# ntp_clock.net
KiCad netlist of a schematic drawn in EAGLE
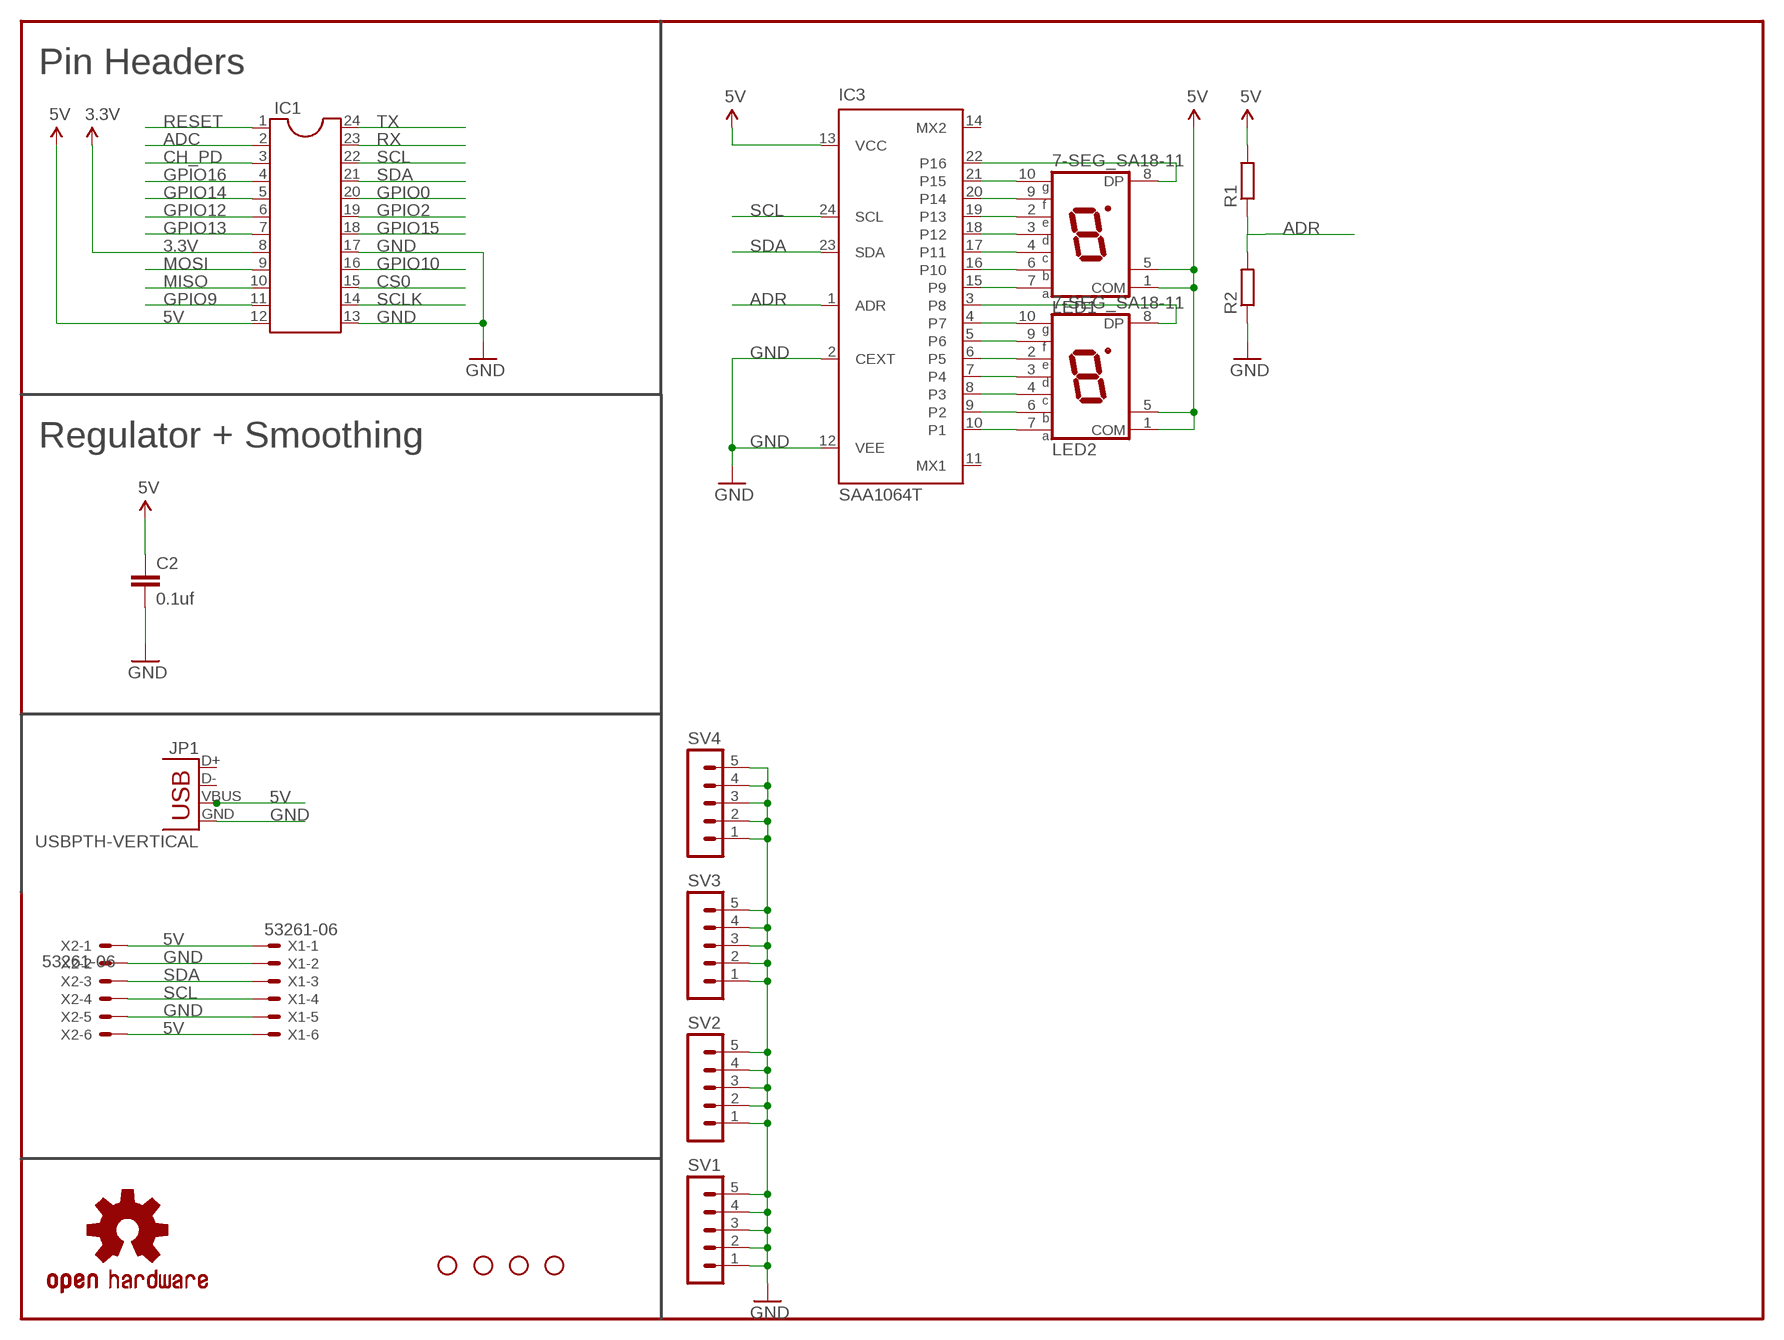
[diagram p0: schematic, sheet 1]

(export (version "E")
  (design (tool "Eeschema 10.0.6"))
  (components
    (comp (ref "C2")
      (value "0.1uf")
      (footprint "eagle-import:1206")
      (libsource (lib "eagle-import") (part "CAP1206"))
    )
    (comp (ref "FRAME1")
      (value "FRAME-LETTERNO_PACKAGE")
      (footprint "eagle-import:DUMMY")
      (fields (field (name "DESIGNER") "Nobody"))
      (libsource (lib "eagle-import") (part "FRAME-LETTERNO_PACKAGE"))
    )
    (comp (ref "IC1")
      (value "DIL24-9")
      (footprint "eagle-import:DIL24-9")
      (libsource (lib "eagle-import") (part "DIL24-9"))
    )
    (comp (ref "IC3")
      (value "SAA1064T")
      (footprint "eagle-import:SO24")
      (fields (field (name "MPN") "SAA1064T/N2,118"))
      (libsource (lib "eagle-import") (part "SAA1064T"))
    )
    (comp (ref "JP1")
      (value "USBPTH-VERTICAL")
      (footprint "eagle-import:USB-B-PTH-VERTICAL")
      (libsource (lib "eagle-import") (part "USBPTH-VERTICAL"))
    )
    (comp (ref "LED1")
      (value "7-SEG_SA18-11")
      (footprint "eagle-import:SA18-11")
      (libsource (lib "eagle-import") (part "7-SEG_SA18-11"))
    )
    (comp (ref "LED2")
      (value "7-SEG_SA18-11")
      (footprint "eagle-import:SA18-11")
      (libsource (lib "eagle-import") (part "7-SEG_SA18-11"))
    )
    (comp (ref "LOGO1")
      (value "OSHW-LOGOS")
      (footprint "eagle-import:OSHW-LOGO-S")
      (libsource (lib "eagle-import") (part "OSHW-LOGOS"))
    )
    (comp (ref "R1")
      (value "R-EU_0207/12")
      (footprint "eagle-import:0207_12")
      (libsource (lib "eagle-import") (part "R-EU_0207/12"))
    )
    (comp (ref "R2")
      (value "R-EU_0207/12")
      (footprint "eagle-import:0207_12")
      (libsource (lib "eagle-import") (part "R-EU_0207/12"))
    )
    (comp (ref "STANDOFF1")
      (value "STAND-OFF")
      (footprint "eagle-import:STAND-OFF")
      (libsource (lib "eagle-import") (part "STAND-OFF"))
    )
    (comp (ref "STANDOFF2")
      (value "STAND-OFF")
      (footprint "eagle-import:STAND-OFF")
      (libsource (lib "eagle-import") (part "STAND-OFF"))
    )
    (comp (ref "STANDOFF3")
      (value "STAND-OFF")
      (footprint "eagle-import:STAND-OFF")
      (libsource (lib "eagle-import") (part "STAND-OFF"))
    )
    (comp (ref "STANDOFF4")
      (value "STAND-OFF")
      (footprint "eagle-import:STAND-OFF")
      (libsource (lib "eagle-import") (part "STAND-OFF"))
    )
    (comp (ref "SV1")
      (value "MA05-1")
      (footprint "eagle-import:MA05-1")
      (libsource (lib "eagle-import") (part "MA05-1"))
    )
    (comp (ref "SV2")
      (value "MA05-1")
      (footprint "eagle-import:MA05-1")
      (libsource (lib "eagle-import") (part "MA05-1"))
    )
    (comp (ref "SV3")
      (value "MA05-1")
      (footprint "eagle-import:MA05-1")
      (libsource (lib "eagle-import") (part "MA05-1"))
    )
    (comp (ref "SV4")
      (value "MA05-1")
      (footprint "eagle-import:MA05-1")
      (libsource (lib "eagle-import") (part "MA05-1"))
    )
    (comp (ref "X1")
      (value "53261-06")
      (footprint "eagle-import:53261-06")
      (libsource (lib "eagle-import") (part "53?-06261"))
    )
    (comp (ref "X2")
      (value "53261-06")
      (footprint "eagle-import:53261-06")
      (libsource (lib "eagle-import") (part "53?-06261"))
    )
  )
  (nets
    (net (code "1") (name "/ADC") (class "Default")
      (node (ref "IC1") (pin "2") (pinfunction "2_2") (pintype "passive"))
    )
    (net (code "2") (name "/ADR") (class "Default")
      (node (ref "IC3") (pin "1") (pinfunction "ADR_1") (pintype "input"))
      (node (ref "R1") (pin "1") (pinfunction "1_1") (pintype "passive"))
      (node (ref "R2") (pin "2") (pinfunction "2_2") (pintype "passive"))
    )
    (net (code "3") (name "/CH_PD") (class "Default")
      (node (ref "IC1") (pin "3") (pinfunction "3_3") (pintype "passive"))
    )
    (net (code "4") (name "/CS0") (class "Default")
      (node (ref "IC1") (pin "15") (pinfunction "15_15") (pintype "passive"))
    )
    (net (code "5") (name "/GPIO0") (class "Default")
      (node (ref "IC1") (pin "20") (pinfunction "20_20") (pintype "passive"))
    )
    (net (code "6") (name "/GPIO2") (class "Default")
      (node (ref "IC1") (pin "19") (pinfunction "19_19") (pintype "passive"))
    )
    (net (code "7") (name "/GPIO9") (class "Default")
      (node (ref "IC1") (pin "11") (pinfunction "11_11") (pintype "passive"))
    )
    (net (code "8") (name "/GPIO10") (class "Default")
      (node (ref "IC1") (pin "16") (pinfunction "16_16") (pintype "passive"))
    )
    (net (code "9") (name "/GPIO12") (class "Default")
      (node (ref "IC1") (pin "6") (pinfunction "6_6") (pintype "passive"))
    )
    (net (code "10") (name "/GPIO13") (class "Default")
      (node (ref "IC1") (pin "7") (pinfunction "7_7") (pintype "passive"))
    )
    (net (code "11") (name "/GPIO14") (class "Default")
      (node (ref "IC1") (pin "5") (pinfunction "5_5") (pintype "passive"))
    )
    (net (code "12") (name "/GPIO15") (class "Default")
      (node (ref "IC1") (pin "18") (pinfunction "18_18") (pintype "passive"))
    )
    (net (code "13") (name "/GPIO16") (class "Default")
      (node (ref "IC1") (pin "4") (pinfunction "4_4") (pintype "passive"))
    )
    (net (code "14") (name "/MISO") (class "Default")
      (node (ref "IC1") (pin "10") (pinfunction "10_10") (pintype "passive"))
    )
    (net (code "15") (name "/MOSI") (class "Default")
      (node (ref "IC1") (pin "9") (pinfunction "9_9") (pintype "passive"))
    )
    (net (code "16") (name "/RESET") (class "Default")
      (node (ref "IC1") (pin "1") (pinfunction "1_1") (pintype "passive"))
    )
    (net (code "17") (name "/RX") (class "Default")
      (node (ref "IC1") (pin "23") (pinfunction "23_23") (pintype "passive"))
    )
    (net (code "18") (name "/SCL") (class "Default")
      (node (ref "IC1") (pin "22") (pinfunction "22_22") (pintype "passive"))
      (node (ref "IC3") (pin "24") (pinfunction "SCL_24") (pintype "input"))
      (node (ref "X1") (pin "4") (pinfunction "S_4") (pintype "passive"))
      (node (ref "X2") (pin "4") (pinfunction "S_4") (pintype "passive"))
    )
    (net (code "19") (name "/SCLK") (class "Default")
      (node (ref "IC1") (pin "14") (pinfunction "14_14") (pintype "passive"))
    )
    (net (code "20") (name "/SDA") (class "Default")
      (node (ref "IC1") (pin "21") (pinfunction "21_21") (pintype "passive"))
      (node (ref "IC3") (pin "23") (pinfunction "SDA_23") (pintype "input"))
      (node (ref "X1") (pin "3") (pinfunction "S_3") (pintype "passive"))
      (node (ref "X2") (pin "3") (pinfunction "S_3") (pintype "passive"))
    )
    (net (code "21") (name "/TX") (class "Default")
      (node (ref "IC1") (pin "24") (pinfunction "24_24") (pintype "passive"))
    )
    (net (code "22") (name "3.3V") (class "Default")
      (node (ref "IC1") (pin "8") (pinfunction "8_8") (pintype "passive"))
    )
    (net (code "23") (name "5V") (class "Default")
      (node (ref "C2") (pin "1") (pinfunction "1_1") (pintype "passive"))
      (node (ref "IC1") (pin "12") (pinfunction "12_12") (pintype "passive"))
      (node (ref "IC3") (pin "13") (pinfunction "VCC_13") (pintype "power_in"))
      (node (ref "JP1") (pin "VBUS") (pinfunction "VBUS_VBUS") (pintype "bidirectional"))
      (node (ref "LED1") (pin "1") (pinfunction "COM_1") (pintype "passive"))
      (node (ref "LED1") (pin "5") (pinfunction "COM_5") (pintype "passive"))
      (node (ref "LED2") (pin "1") (pinfunction "COM_1") (pintype "passive"))
      (node (ref "LED2") (pin "5") (pinfunction "COM_5") (pintype "passive"))
      (node (ref "R1") (pin "2") (pinfunction "2_2") (pintype "passive"))
      (node (ref "X1") (pin "1") (pinfunction "S_1") (pintype "passive"))
      (node (ref "X1") (pin "6") (pinfunction "S_6") (pintype "passive"))
      (node (ref "X2") (pin "1") (pinfunction "S_1") (pintype "passive"))
      (node (ref "X2") (pin "6") (pinfunction "S_6") (pintype "passive"))
    )
    (net (code "24") (name "GND") (class "Default")
      (node (ref "C2") (pin "2") (pinfunction "2_2") (pintype "passive"))
      (node (ref "IC1") (pin "13") (pinfunction "13_13") (pintype "passive"))
      (node (ref "IC1") (pin "17") (pinfunction "17_17") (pintype "passive"))
      (node (ref "IC3") (pin "12") (pinfunction "VEE_12") (pintype "power_in"))
      (node (ref "IC3") (pin "2") (pinfunction "CEXT_2") (pintype "input"))
      (node (ref "JP1") (pin "GND") (pinfunction "GND_GND") (pintype "bidirectional"))
      (node (ref "R2") (pin "1") (pinfunction "1_1") (pintype "passive"))
      (node (ref "SV1") (pin "1") (pinfunction "1_1") (pintype "passive"))
      (node (ref "SV1") (pin "2") (pinfunction "2_2") (pintype "passive"))
      (node (ref "SV1") (pin "3") (pinfunction "3_3") (pintype "passive"))
      (node (ref "SV1") (pin "4") (pinfunction "4_4") (pintype "passive"))
      (node (ref "SV1") (pin "5") (pinfunction "5_5") (pintype "passive"))
      (node (ref "SV2") (pin "1") (pinfunction "1_1") (pintype "passive"))
      (node (ref "SV2") (pin "2") (pinfunction "2_2") (pintype "passive"))
      (node (ref "SV2") (pin "3") (pinfunction "3_3") (pintype "passive"))
      (node (ref "SV2") (pin "4") (pinfunction "4_4") (pintype "passive"))
      (node (ref "SV2") (pin "5") (pinfunction "5_5") (pintype "passive"))
      (node (ref "SV3") (pin "1") (pinfunction "1_1") (pintype "passive"))
      (node (ref "SV3") (pin "2") (pinfunction "2_2") (pintype "passive"))
      (node (ref "SV3") (pin "3") (pinfunction "3_3") (pintype "passive"))
      (node (ref "SV3") (pin "4") (pinfunction "4_4") (pintype "passive"))
      (node (ref "SV3") (pin "5") (pinfunction "5_5") (pintype "passive"))
      (node (ref "SV4") (pin "1") (pinfunction "1_1") (pintype "passive"))
      (node (ref "SV4") (pin "2") (pinfunction "2_2") (pintype "passive"))
      (node (ref "SV4") (pin "3") (pinfunction "3_3") (pintype "passive"))
      (node (ref "SV4") (pin "4") (pinfunction "4_4") (pintype "passive"))
      (node (ref "SV4") (pin "5") (pinfunction "5_5") (pintype "passive"))
      (node (ref "X1") (pin "2") (pinfunction "S_2") (pintype "passive"))
      (node (ref "X1") (pin "5") (pinfunction "S_5") (pintype "passive"))
      (node (ref "X2") (pin "2") (pinfunction "S_2") (pintype "passive"))
      (node (ref "X2") (pin "5") (pinfunction "S_5") (pintype "passive"))
    )
    (net (code "25") (name "Net-(IC3-P1)") (class "Default")
      (node (ref "IC3") (pin "10") (pinfunction "P1_10") (pintype "output"))
      (node (ref "LED2") (pin "7") (pinfunction "A_7") (pintype "passive"))
    )
    (net (code "26") (name "Net-(IC3-P2)") (class "Default")
      (node (ref "IC3") (pin "9") (pinfunction "P2_9") (pintype "output"))
      (node (ref "LED2") (pin "6") (pinfunction "B_6") (pintype "passive"))
    )
    (net (code "27") (name "Net-(IC3-P3)") (class "Default")
      (node (ref "IC3") (pin "8") (pinfunction "P3_8") (pintype "output"))
      (node (ref "LED2") (pin "4") (pinfunction "C_4") (pintype "passive"))
    )
    (net (code "28") (name "Net-(IC3-P4)") (class "Default")
      (node (ref "IC3") (pin "7") (pinfunction "P4_7") (pintype "output"))
      (node (ref "LED2") (pin "3") (pinfunction "D_3") (pintype "passive"))
    )
    (net (code "29") (name "Net-(IC3-P5)") (class "Default")
      (node (ref "IC3") (pin "6") (pinfunction "P5_6") (pintype "output"))
      (node (ref "LED2") (pin "2") (pinfunction "E_2") (pintype "passive"))
    )
    (net (code "30") (name "Net-(IC3-P6)") (class "Default")
      (node (ref "IC3") (pin "5") (pinfunction "P6_5") (pintype "output"))
      (node (ref "LED2") (pin "9") (pinfunction "F_9") (pintype "passive"))
    )
    (net (code "31") (name "Net-(IC3-P7)") (class "Default")
      (node (ref "IC3") (pin "4") (pinfunction "P7_4") (pintype "output"))
      (node (ref "LED2") (pin "10") (pinfunction "G_10") (pintype "passive"))
    )
    (net (code "32") (name "Net-(IC3-P8)") (class "Default")
      (node (ref "IC3") (pin "3") (pinfunction "P8_3") (pintype "output"))
      (node (ref "LED2") (pin "8") (pinfunction "DP_8") (pintype "passive"))
    )
    (net (code "33") (name "Net-(IC3-P9)") (class "Default")
      (node (ref "IC3") (pin "15") (pinfunction "P9_15") (pintype "output"))
      (node (ref "LED1") (pin "7") (pinfunction "A_7") (pintype "passive"))
    )
    (net (code "34") (name "Net-(IC3-P10)") (class "Default")
      (node (ref "IC3") (pin "16") (pinfunction "P10_16") (pintype "output"))
      (node (ref "LED1") (pin "6") (pinfunction "B_6") (pintype "passive"))
    )
    (net (code "35") (name "Net-(IC3-P11)") (class "Default")
      (node (ref "IC3") (pin "17") (pinfunction "P11_17") (pintype "output"))
      (node (ref "LED1") (pin "4") (pinfunction "C_4") (pintype "passive"))
    )
    (net (code "36") (name "Net-(IC3-P12)") (class "Default")
      (node (ref "IC3") (pin "18") (pinfunction "P12_18") (pintype "output"))
      (node (ref "LED1") (pin "3") (pinfunction "D_3") (pintype "passive"))
    )
    (net (code "37") (name "Net-(IC3-P13)") (class "Default")
      (node (ref "IC3") (pin "19") (pinfunction "P13_19") (pintype "output"))
      (node (ref "LED1") (pin "2") (pinfunction "E_2") (pintype "passive"))
    )
    (net (code "38") (name "Net-(IC3-P14)") (class "Default")
      (node (ref "IC3") (pin "20") (pinfunction "P14_20") (pintype "output"))
      (node (ref "LED1") (pin "9") (pinfunction "F_9") (pintype "passive"))
    )
    (net (code "39") (name "Net-(IC3-P15)") (class "Default")
      (node (ref "IC3") (pin "21") (pinfunction "P15_21") (pintype "output"))
      (node (ref "LED1") (pin "10") (pinfunction "G_10") (pintype "passive"))
    )
    (net (code "40") (name "Net-(IC3-P16)") (class "Default")
      (node (ref "IC3") (pin "22") (pinfunction "P16_22") (pintype "output"))
      (node (ref "LED1") (pin "8") (pinfunction "DP_8") (pintype "passive"))
    )
    (net (code "41") (name "unconnected-(IC3-MX1-Pad11)") (class "Default")
      (node (ref "IC3") (pin "11") (pinfunction "MX1_11") (pintype "output"))
    )
    (net (code "42") (name "unconnected-(IC3-MX2-Pad14)") (class "Default")
      (node (ref "IC3") (pin "14") (pinfunction "MX2_14") (pintype "output"))
    )
    (net (code "43") (name "unconnected-(JP1-PadD+)") (class "Default")
      (node (ref "JP1") (pin "D+") (pinfunction "D+_D+") (pintype "bidirectional"))
    )
    (net (code "44") (name "unconnected-(JP1-PadD-)") (class "Default")
      (node (ref "JP1") (pin "D-") (pinfunction "D-_D-") (pintype "bidirectional"))
    )
  )
)
